# Mynd_Main.net
KiCad netlist of a schematic drawn in Altium Designer
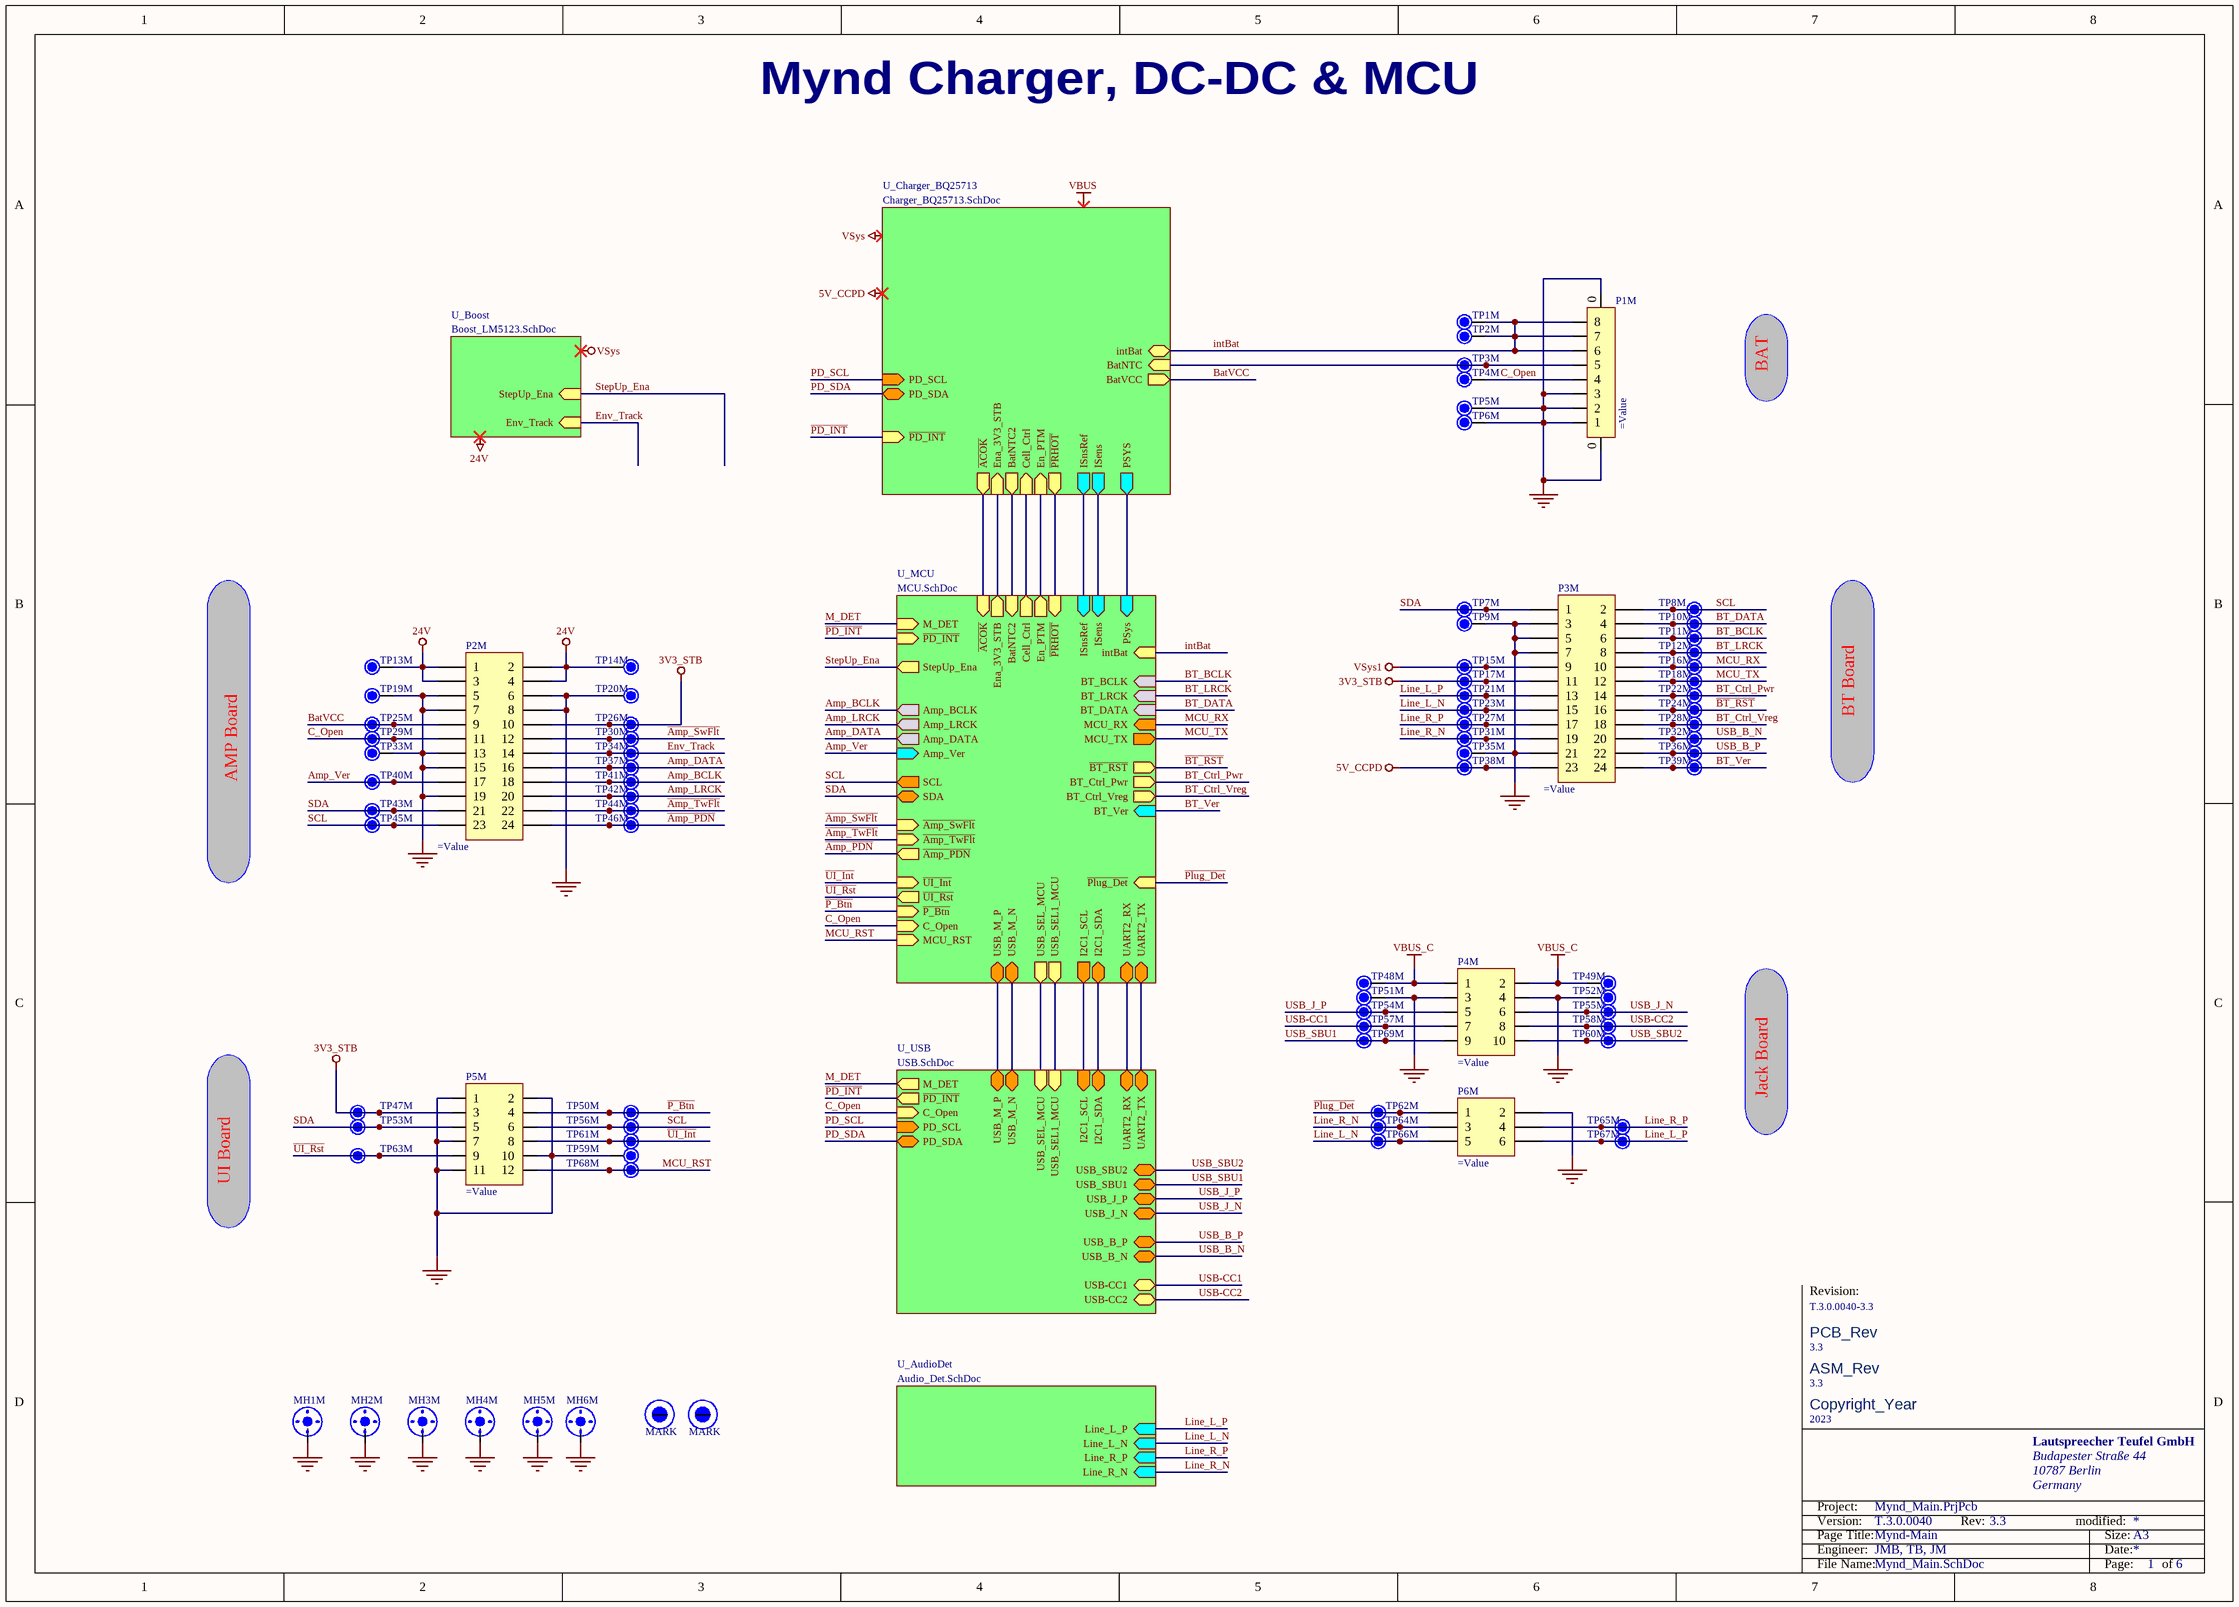
[diagram p0: Mynd_Main.SchDoc]

(export (version "E")
  (design (tool "Eeschema 10.0.6"))
  (components
    (comp (ref "MH1M")
      (value "SCREW_HOLE_D30")
      (footprint "SCREW_D30")
      (libsource (lib "altium-import") (part "root_1_SCREW_HOLE_"))
    )
    (comp (ref "MH2M")
      (value "SCREW_HOLE_D30")
      (footprint "SCREW_D30")
      (libsource (lib "altium-import") (part "root_1_SCREW_HOLE_"))
    )
    (comp (ref "MH3M")
      (value "SCREW_HOLE_D30")
      (footprint "SCREW_D30")
      (libsource (lib "altium-import") (part "root_1_SCREW_HOLE_"))
    )
    (comp (ref "MH4M")
      (value "SCREW_HOLE_D30")
      (footprint "SCREW_D30")
      (libsource (lib "altium-import") (part "root_1_SCREW_HOLE_"))
    )
    (comp (ref "MH5M")
      (value "SCREW_HOLE_D30")
      (footprint "SCREW_D30")
      (libsource (lib "altium-import") (part "root_1_SCREW_HOLE_"))
    )
    (comp (ref "MH6M")
      (value "SCREW_HOLE_D30")
      (footprint "SCREW_D30")
      (libsource (lib "altium-import") (part "root_1_SCREW_HOLE_"))
    )
    (comp (ref "MK1M")
      (value "MARK")
      (footprint "MARK")
      (description "MARK DOT")
      (libsource (lib "altium-import") (part "root_0_MARK_"))
    )
    (comp (ref "MK2M")
      (value "MARK")
      (footprint "MARK")
      (description "MARK DOT")
      (libsource (lib "altium-import") (part "root_0_MARK_"))
    )
    (comp (ref "P1M")
      (value "~")
      (footprint "CON_250_SMD_H_8P")
      (description "SMD WTB CONNECTOR 8P P2.5mm TIN")
      (fields (field (name "PART_NUMBER") "WT250MW-084R-0W"))
      (libsource (lib "altium-import") (part "root_2_CON 8P_F_"))
    )
    (comp (ref "P2M")
      (value "~")
      (footprint "Female_SMD_Bottom_2X12_254")
      (description "SMD BTB CONNECTOR 24P P2.54mm GOLD")
      (fields
        (field (name "MANUFACTURER") "MINGHENG")
        (field (name "PART_NUMBER") "2.54FH 2x12Pin H3.55 SMT")
      )
      (libsource (lib "altium-import") (part "root_0_CON 2x12P_"))
    )
    (comp (ref "P3M")
      (value "~")
      (footprint "Female_SMD_Bottom_2X12_254")
      (description "SMD BTB CONNECTOR 24P P2.54mm GOLD")
      (fields
        (field (name "MANUFACTURER") "MINGHENG")
        (field (name "PART_NUMBER") "2.54FH 2x12Pin H3.55 SMT")
      )
      (libsource (lib "altium-import") (part "root_0_CON 2x12P_"))
    )
    (comp (ref "P4M")
      (value "~")
      (footprint "WB200AL_2x5P")
      (description "SMD WTB CONNECTOR 10P P2.0mm TIN")
      (fields (field (name "MANUFACTURER") "MINGHENG") (field (name "PART_NUMBER") "WB200AL-10"))
      (libsource (lib "altium-import") (part "root_0_CON 2X5P_"))
    )
    (comp (ref "P5M")
      (value "~")
      (footprint "WB200AL_2x6P")
      (description "SMD WTB CONNECTOR 12P P2.0mm TIN")
      (fields (field (name "MANUFACTURER") "MINGHENG") (field (name "PART_NUMBER") "WB200AL-12"))
      (libsource (lib "altium-import") (part "root_0_CON 2X6P_"))
    )
    (comp (ref "P6M")
      (value "~")
      (footprint "WB200AL_2x3P")
      (description "SMD WTB CONNECTOR 6P P2.0mm TIN")
      (fields (field (name "MANUFACTURER") "MINGHENG") (field (name "PART_NUMBER") "WB200AL-06"))
      (libsource (lib "altium-import") (part "root_0_CON 2X3P_"))
    )
    (comp (ref "Teufel_ASM_Label1M")
      (value "3.3")
      (footprint "Teufel_ASM_Rev")
      (description "Teufel_ASM_Rev")
      (libsource (lib "altium-import") (part "root_0_Teufel_ASM_Label_"))
    )
    (comp (ref "Teufel_Copyright1M")
      (value "~")
      (footprint "TEUFEL_COPYRIGHT")
      (description "Teufel_Copyright_Year")
      (libsource (lib "altium-import") (part "root_0_Teufel_Copyright_"))
    )
    (comp (ref "Teufel_PCB_Label1M")
      (value "3.3")
      (footprint "Teufel_PCB_Rev")
      (description "Teufel_PCB_Label")
      (libsource (lib "altium-import") (part "root_0_Teufel_PCB_Label_"))
    )
    (comp (ref "Teufel_PCB_Logo1M")
      (value "-3.3")
      (footprint "Teufel_NoLogo")
      (description "Teufel PCB NoLogo")
      (libsource (lib "altium-import") (part "root_0_Teufel NoLogo_"))
    )
    (comp (ref "TP1M")
      (value "TP12")
      (footprint "TP120")
      (description "Test Point")
      (libsource (lib "altium-import") (part "root_0_mirrored_TP_"))
    )
    (comp (ref "TP2M")
      (value "TP12")
      (footprint "TP120")
      (description "Test Point")
      (libsource (lib "altium-import") (part "root_0_mirrored_TP_"))
    )
    (comp (ref "TP3M")
      (value "TP12")
      (footprint "TP120")
      (description "Test Point")
      (libsource (lib "altium-import") (part "root_0_mirrored_TP_"))
    )
    (comp (ref "TP4M")
      (value "TP12")
      (footprint "TP120")
      (description "Test Point")
      (libsource (lib "altium-import") (part "root_0_mirrored_TP_"))
    )
    (comp (ref "TP5M")
      (value "TP12")
      (footprint "TP120")
      (description "Test Point")
      (libsource (lib "altium-import") (part "root_0_mirrored_TP_"))
    )
    (comp (ref "TP6M")
      (value "TP12")
      (footprint "TP120")
      (description "Test Point")
      (libsource (lib "altium-import") (part "root_0_mirrored_TP_"))
    )
    (comp (ref "TP7M")
      (value "TP12")
      (footprint "TP120")
      (description "Test Point")
      (libsource (lib "altium-import") (part "root_0_mirrored_TP_"))
    )
    (comp (ref "TP8M")
      (value "TP12")
      (footprint "TP120")
      (description "Test Point")
      (libsource (lib "altium-import") (part "root_0_TP_"))
    )
    (comp (ref "TP9M")
      (value "TP12")
      (footprint "TP120")
      (description "Test Point")
      (libsource (lib "altium-import") (part "root_0_mirrored_TP_"))
    )
    (comp (ref "TP10M")
      (value "TP12")
      (footprint "TP120")
      (description "Test Point")
      (libsource (lib "altium-import") (part "root_0_TP_"))
    )
    (comp (ref "TP11M")
      (value "TP12")
      (footprint "TP120")
      (description "Test Point")
      (libsource (lib "altium-import") (part "root_0_TP_"))
    )
    (comp (ref "TP12M")
      (value "TP12")
      (footprint "TP120")
      (description "Test Point")
      (libsource (lib "altium-import") (part "root_0_TP_"))
    )
    (comp (ref "TP13M")
      (value "TP12")
      (footprint "TP120")
      (description "Test Point")
      (libsource (lib "altium-import") (part "root_0_mirrored_TP_"))
    )
    (comp (ref "TP14M")
      (value "TP12")
      (footprint "TP120")
      (description "Test Point")
      (libsource (lib "altium-import") (part "root_0_TP_"))
    )
    (comp (ref "TP15M")
      (value "TP12")
      (footprint "TP120")
      (description "Test Point")
      (libsource (lib "altium-import") (part "root_0_mirrored_TP_"))
    )
    (comp (ref "TP16M")
      (value "TP12")
      (footprint "TP120")
      (description "Test Point")
      (libsource (lib "altium-import") (part "root_0_TP_"))
    )
    (comp (ref "TP17M")
      (value "TP12")
      (footprint "TP120")
      (description "Test Point")
      (libsource (lib "altium-import") (part "root_0_mirrored_TP_"))
    )
    (comp (ref "TP18M")
      (value "TP12")
      (footprint "TP120")
      (description "Test Point")
      (libsource (lib "altium-import") (part "root_0_TP_"))
    )
    (comp (ref "TP19M")
      (value "TP12")
      (footprint "TP120")
      (description "Test Point")
      (libsource (lib "altium-import") (part "root_0_mirrored_TP_"))
    )
    (comp (ref "TP20M")
      (value "TP12")
      (footprint "TP120")
      (description "Test Point")
      (libsource (lib "altium-import") (part "root_0_TP_"))
    )
    (comp (ref "TP21M")
      (value "TP12")
      (footprint "TP120")
      (description "Test Point")
      (libsource (lib "altium-import") (part "root_0_mirrored_TP_"))
    )
    (comp (ref "TP22M")
      (value "TP12")
      (footprint "TP120")
      (description "Test Point")
      (libsource (lib "altium-import") (part "root_0_TP_"))
    )
    (comp (ref "TP23M")
      (value "TP12")
      (footprint "TP120")
      (description "Test Point")
      (libsource (lib "altium-import") (part "root_0_mirrored_TP_"))
    )
    (comp (ref "TP24M")
      (value "TP12")
      (footprint "TP120")
      (description "Test Point")
      (libsource (lib "altium-import") (part "root_0_TP_"))
    )
    (comp (ref "TP25M")
      (value "TP12")
      (footprint "TP120")
      (description "Test Point")
      (libsource (lib "altium-import") (part "root_0_mirrored_TP_"))
    )
    (comp (ref "TP26M")
      (value "TP12")
      (footprint "TP120")
      (description "Test Point")
      (libsource (lib "altium-import") (part "root_0_TP_"))
    )
    (comp (ref "TP27M")
      (value "TP12")
      (footprint "TP120")
      (description "Test Point")
      (libsource (lib "altium-import") (part "root_0_mirrored_TP_"))
    )
    (comp (ref "TP28M")
      (value "TP12")
      (footprint "TP120")
      (description "Test Point")
      (libsource (lib "altium-import") (part "root_0_TP_"))
    )
    (comp (ref "TP29M")
      (value "TP12")
      (footprint "TP120")
      (description "Test Point")
      (libsource (lib "altium-import") (part "root_0_mirrored_TP_"))
    )
    (comp (ref "TP30M")
      (value "TP12")
      (footprint "TP120")
      (description "Test Point")
      (libsource (lib "altium-import") (part "root_0_TP_"))
    )
    (comp (ref "TP31M")
      (value "TP12")
      (footprint "TP120")
      (description "Test Point")
      (libsource (lib "altium-import") (part "root_0_mirrored_TP_"))
    )
    (comp (ref "TP32M")
      (value "TP12")
      (footprint "TP120")
      (description "Test Point")
      (libsource (lib "altium-import") (part "root_0_TP_"))
    )
    (comp (ref "TP33M")
      (value "TP12")
      (footprint "TP120")
      (description "Test Point")
      (libsource (lib "altium-import") (part "root_0_mirrored_TP_"))
    )
    (comp (ref "TP34M")
      (value "TP12")
      (footprint "TP120")
      (description "Test Point")
      (libsource (lib "altium-import") (part "root_0_TP_"))
    )
    (comp (ref "TP35M")
      (value "TP12")
      (footprint "TP120")
      (description "Test Point")
      (libsource (lib "altium-import") (part "root_0_mirrored_TP_"))
    )
    (comp (ref "TP36M")
      (value "TP12")
      (footprint "TP120")
      (description "Test Point")
      (libsource (lib "altium-import") (part "root_0_TP_"))
    )
    (comp (ref "TP37M")
      (value "TP12")
      (footprint "TP120")
      (description "Test Point")
      (libsource (lib "altium-import") (part "root_0_TP_"))
    )
    (comp (ref "TP38M")
      (value "TP12")
      (footprint "TP120")
      (description "Test Point")
      (libsource (lib "altium-import") (part "root_0_mirrored_TP_"))
    )
    (comp (ref "TP39M")
      (value "TP12")
      (footprint "TP120")
      (description "Test Point")
      (libsource (lib "altium-import") (part "root_0_TP_"))
    )
    (comp (ref "TP40M")
      (value "TP12")
      (footprint "TP120")
      (description "Test Point")
      (libsource (lib "altium-import") (part "root_0_mirrored_TP_"))
    )
    (comp (ref "TP41M")
      (value "TP12")
      (footprint "TP120")
      (description "Test Point")
      (libsource (lib "altium-import") (part "root_0_TP_"))
    )
    (comp (ref "TP42M")
      (value "TP12")
      (footprint "TP120")
      (description "Test Point")
      (libsource (lib "altium-import") (part "root_0_TP_"))
    )
    (comp (ref "TP43M")
      (value "TP12")
      (footprint "TP120")
      (description "Test Point")
      (libsource (lib "altium-import") (part "root_0_mirrored_TP_"))
    )
    (comp (ref "TP44M")
      (value "TP12")
      (footprint "TP120")
      (description "Test Point")
      (libsource (lib "altium-import") (part "root_0_TP_"))
    )
    (comp (ref "TP45M")
      (value "TP12")
      (footprint "TP120")
      (description "Test Point")
      (libsource (lib "altium-import") (part "root_0_mirrored_TP_"))
    )
    (comp (ref "TP46M")
      (value "TP12")
      (footprint "TP120")
      (description "Test Point")
      (libsource (lib "altium-import") (part "root_0_TP_"))
    )
    (comp (ref "TP47M")
      (value "TP12")
      (footprint "TP120")
      (description "Test Point")
      (libsource (lib "altium-import") (part "root_0_mirrored_TP_"))
    )
    (comp (ref "TP48M")
      (value "TP12")
      (footprint "TP120")
      (description "Test Point")
      (libsource (lib "altium-import") (part "root_0_mirrored_TP_"))
    )
    (comp (ref "TP49M")
      (value "TP12")
      (footprint "TP120")
      (description "Test Point")
      (libsource (lib "altium-import") (part "root_0_TP_"))
    )
    (comp (ref "TP50M")
      (value "TP12")
      (footprint "TP120")
      (description "Test Point")
      (libsource (lib "altium-import") (part "root_0_TP_"))
    )
    (comp (ref "TP51M")
      (value "TP12")
      (footprint "TP120")
      (description "Test Point")
      (libsource (lib "altium-import") (part "root_0_mirrored_TP_"))
    )
    (comp (ref "TP52M")
      (value "TP12")
      (footprint "TP120")
      (description "Test Point")
      (libsource (lib "altium-import") (part "root_0_TP_"))
    )
    (comp (ref "TP53M")
      (value "TP12")
      (footprint "TP120")
      (description "Test Point")
      (libsource (lib "altium-import") (part "root_0_mirrored_TP_"))
    )
    (comp (ref "TP54M")
      (value "TP12")
      (footprint "TP120")
      (description "Test Point")
      (libsource (lib "altium-import") (part "root_0_mirrored_TP_"))
    )
    (comp (ref "TP55M")
      (value "TP12")
      (footprint "TP120")
      (description "Test Point")
      (libsource (lib "altium-import") (part "root_0_TP_"))
    )
    (comp (ref "TP56M")
      (value "TP12")
      (footprint "TP120")
      (description "Test Point")
      (libsource (lib "altium-import") (part "root_0_TP_"))
    )
    (comp (ref "TP57M")
      (value "TP12")
      (footprint "TP120")
      (description "Test Point")
      (libsource (lib "altium-import") (part "root_0_mirrored_TP_"))
    )
    (comp (ref "TP58M")
      (value "TP12")
      (footprint "TP120")
      (description "Test Point")
      (libsource (lib "altium-import") (part "root_0_TP_"))
    )
    (comp (ref "TP59M")
      (value "TP12")
      (footprint "TP120")
      (description "Test Point")
      (libsource (lib "altium-import") (part "root_0_TP_"))
    )
    (comp (ref "TP60M")
      (value "TP12")
      (footprint "TP120")
      (description "Test Point")
      (libsource (lib "altium-import") (part "root_0_TP_"))
    )
    (comp (ref "TP61M")
      (value "TP12")
      (footprint "TP120")
      (description "Test Point")
      (libsource (lib "altium-import") (part "root_0_TP_"))
    )
    (comp (ref "TP62M")
      (value "TP12")
      (footprint "TP120")
      (description "Test Point")
      (libsource (lib "altium-import") (part "root_0_mirrored_TP_"))
    )
    (comp (ref "TP63M")
      (value "TP12")
      (footprint "TP120")
      (description "Test Point")
      (libsource (lib "altium-import") (part "root_0_mirrored_TP_"))
    )
    (comp (ref "TP64M")
      (value "TP12")
      (footprint "TP120")
      (description "Test Point")
      (libsource (lib "altium-import") (part "root_0_mirrored_TP_"))
    )
    (comp (ref "TP65M")
      (value "TP12")
      (footprint "TP120")
      (description "Test Point")
      (libsource (lib "altium-import") (part "root_0_TP_"))
    )
    (comp (ref "TP66M")
      (value "TP12")
      (footprint "TP120")
      (description "Test Point")
      (libsource (lib "altium-import") (part "root_0_mirrored_TP_"))
    )
    (comp (ref "TP67M")
      (value "TP12")
      (footprint "TP120")
      (description "Test Point")
      (libsource (lib "altium-import") (part "root_0_TP_"))
    )
    (comp (ref "TP68M")
      (value "TP12")
      (footprint "TP120")
      (description "Test Point")
      (libsource (lib "altium-import") (part "root_0_TP_"))
    )
    (comp (ref "TP69M")
      (value "TP12")
      (footprint "TP120")
      (description "Test Point")
      (libsource (lib "altium-import") (part "root_0_mirrored_TP_"))
    )
  )
  (nets
    (net (code "2") (name "/Amp_BCLK") (class "Default")
      (node (ref "P2M") (pin "18") (pinfunction "18_18") (pintype "passive"))
      (node (ref "TP41M") (pin "1") (pinfunction "1_1") (pintype "passive"))
    )
    (net (code "3") (name "/Amp_DATA") (class "Default")
      (node (ref "P2M") (pin "16") (pinfunction "16_16") (pintype "passive"))
      (node (ref "TP37M") (pin "1") (pinfunction "1_1") (pintype "passive"))
    )
    (net (code "4") (name "/Amp_LRCK") (class "Default")
      (node (ref "P2M") (pin "20") (pinfunction "20_20") (pintype "passive"))
      (node (ref "TP42M") (pin "1") (pinfunction "1_1") (pintype "passive"))
    )
    (net (code "5") (name "/Amp_Ver") (class "Default")
      (node (ref "P2M") (pin "17") (pinfunction "17_17") (pintype "passive"))
      (node (ref "TP40M") (pin "1") (pinfunction "1_1") (pintype "passive"))
    )
    (net (code "6") (name "/BT_BCLK") (class "Default")
      (node (ref "P3M") (pin "6") (pinfunction "6_6") (pintype "passive"))
      (node (ref "TP11M") (pin "1") (pinfunction "1_1") (pintype "passive"))
    )
    (net (code "7") (name "/BT_Ctrl_Pwr") (class "Default")
      (node (ref "P3M") (pin "14") (pinfunction "14_14") (pintype "passive"))
      (node (ref "TP22M") (pin "1") (pinfunction "1_1") (pintype "passive"))
    )
    (net (code "8") (name "/BT_Ctrl_Vreg") (class "Default")
      (node (ref "P3M") (pin "18") (pinfunction "18_18") (pintype "passive"))
      (node (ref "TP28M") (pin "1") (pinfunction "1_1") (pintype "passive"))
    )
    (net (code "9") (name "/BT_DATA") (class "Default")
      (node (ref "P3M") (pin "4") (pinfunction "4_4") (pintype "passive"))
      (node (ref "TP10M") (pin "1") (pinfunction "1_1") (pintype "passive"))
    )
    (net (code "10") (name "/BT_LRCK") (class "Default")
      (node (ref "P3M") (pin "8") (pinfunction "8_8") (pintype "passive"))
      (node (ref "TP12M") (pin "1") (pinfunction "1_1") (pintype "passive"))
    )
    (net (code "11") (name "/BT_RST") (class "Default")
      (node (ref "P3M") (pin "16") (pinfunction "16_16") (pintype "passive"))
      (node (ref "TP24M") (pin "1") (pinfunction "1_1") (pintype "passive"))
    )
    (net (code "12") (name "/BT_Ver") (class "Default")
      (node (ref "P3M") (pin "24") (pinfunction "24_24") (pintype "passive"))
      (node (ref "TP39M") (pin "1") (pinfunction "1_1") (pintype "passive"))
    )
    (net (code "13") (name "/BatNTC") (class "Default")
      (node (ref "P1M") (pin "5") (pinfunction "5_5") (pintype "passive"))
      (node (ref "TP3M") (pin "1") (pinfunction "1_1") (pintype "passive"))
    )
    (net (code "15") (name "/BatVCC") (class "Default")
      (node (ref "P2M") (pin "9") (pinfunction "9_9") (pintype "passive"))
      (node (ref "TP25M") (pin "1") (pinfunction "1_1") (pintype "passive"))
    )
    (net (code "16") (name "/C_Open") (class "Default")
      (node (ref "P1M") (pin "4") (pinfunction "4_4") (pintype "passive"))
      (node (ref "P2M") (pin "11") (pinfunction "11_11") (pintype "passive"))
      (node (ref "TP29M") (pin "1") (pinfunction "1_1") (pintype "passive"))
      (node (ref "TP4M") (pin "1") (pinfunction "1_1") (pintype "passive"))
    )
    (net (code "20") (name "/Env_Track") (class "Default")
      (node (ref "P2M") (pin "14") (pinfunction "14_14") (pintype "passive"))
      (node (ref "TP34M") (pin "1") (pinfunction "1_1") (pintype "passive"))
    )
    (net (code "25") (name "/Line_L_N") (class "Default")
      (node (ref "P3M") (pin "15") (pinfunction "15_15") (pintype "passive"))
      (node (ref "P6M") (pin "5") (pinfunction "5_5") (pintype "passive"))
      (node (ref "TP23M") (pin "1") (pinfunction "1_1") (pintype "passive"))
      (node (ref "TP66M") (pin "1") (pinfunction "1_1") (pintype "passive"))
    )
    (net (code "26") (name "/Line_L_P") (class "Default")
      (node (ref "P3M") (pin "13") (pinfunction "13_13") (pintype "passive"))
      (node (ref "P6M") (pin "6") (pinfunction "6_6") (pintype "passive"))
      (node (ref "TP21M") (pin "1") (pinfunction "1_1") (pintype "passive"))
      (node (ref "TP67M") (pin "1") (pinfunction "1_1") (pintype "passive"))
    )
    (net (code "27") (name "/Line_R_N") (class "Default")
      (node (ref "P3M") (pin "19") (pinfunction "19_19") (pintype "passive"))
      (node (ref "P6M") (pin "3") (pinfunction "3_3") (pintype "passive"))
      (node (ref "TP31M") (pin "1") (pinfunction "1_1") (pintype "passive"))
      (node (ref "TP64M") (pin "1") (pinfunction "1_1") (pintype "passive"))
    )
    (net (code "28") (name "/Line_R_P") (class "Default")
      (node (ref "P3M") (pin "17") (pinfunction "17_17") (pintype "passive"))
      (node (ref "P6M") (pin "4") (pinfunction "4_4") (pintype "passive"))
      (node (ref "TP27M") (pin "1") (pinfunction "1_1") (pintype "passive"))
      (node (ref "TP65M") (pin "1") (pinfunction "1_1") (pintype "passive"))
    )
    (net (code "29") (name "/MCU_RST") (class "Default")
      (node (ref "P5M") (pin "12") (pinfunction "12_12") (pintype "passive"))
      (node (ref "TP68M") (pin "1") (pinfunction "1_1") (pintype "passive"))
    )
    (net (code "30") (name "/MCU_RX") (class "Default")
      (node (ref "P3M") (pin "10") (pinfunction "10_10") (pintype "passive"))
      (node (ref "TP16M") (pin "1") (pinfunction "1_1") (pintype "passive"))
    )
    (net (code "31") (name "/MCU_TX") (class "Default")
      (node (ref "P3M") (pin "12") (pinfunction "12_12") (pintype "passive"))
      (node (ref "TP18M") (pin "1") (pinfunction "1_1") (pintype "passive"))
    )
    (net (code "38") (name "/P_Btn") (class "Default")
      (node (ref "P5M") (pin "4") (pinfunction "4_4") (pintype "passive"))
      (node (ref "TP50M") (pin "1") (pinfunction "1_1") (pintype "passive"))
    )
    (net (code "39") (name "/Plug_Det") (class "Default")
      (node (ref "P6M") (pin "1") (pinfunction "1_1") (pintype "passive"))
      (node (ref "TP62M") (pin "1") (pinfunction "1_1") (pintype "passive"))
    )
    (net (code "40") (name "/SCL") (class "Default")
      (node (ref "P2M") (pin "23") (pinfunction "23_23") (pintype "passive"))
      (node (ref "P3M") (pin "2") (pinfunction "2_2") (pintype "passive"))
      (node (ref "P5M") (pin "6") (pinfunction "6_6") (pintype "passive"))
      (node (ref "TP45M") (pin "1") (pinfunction "1_1") (pintype "passive"))
      (node (ref "TP56M") (pin "1") (pinfunction "1_1") (pintype "passive"))
      (node (ref "TP8M") (pin "1") (pinfunction "1_1") (pintype "passive"))
    )
    (net (code "41") (name "/SDA") (class "Default")
      (node (ref "P2M") (pin "21") (pinfunction "21_21") (pintype "passive"))
      (node (ref "P3M") (pin "1") (pinfunction "1_1") (pintype "passive"))
      (node (ref "P5M") (pin "5") (pinfunction "5_5") (pintype "passive"))
      (node (ref "TP43M") (pin "1") (pinfunction "1_1") (pintype "passive"))
      (node (ref "TP53M") (pin "1") (pinfunction "1_1") (pintype "passive"))
      (node (ref "TP7M") (pin "1") (pinfunction "1_1") (pintype "passive"))
    )
    (net (code "45") (name "/UI_Int") (class "Default")
      (node (ref "P5M") (pin "8") (pinfunction "8_8") (pintype "passive"))
      (node (ref "TP61M") (pin "1") (pinfunction "1_1") (pintype "passive"))
    )
    (net (code "46") (name "/UI_Rst") (class "Default")
      (node (ref "P5M") (pin "9") (pinfunction "9_9") (pintype "passive"))
      (node (ref "TP63M") (pin "1") (pinfunction "1_1") (pintype "passive"))
    )
    (net (code "47") (name "/USB-CC1") (class "Default")
      (node (ref "P4M") (pin "7") (pinfunction "7_7") (pintype "passive"))
      (node (ref "TP57M") (pin "1") (pinfunction "1_1") (pintype "passive"))
    )
    (net (code "48") (name "/USB-CC2") (class "Default")
      (node (ref "P4M") (pin "8") (pinfunction "8_8") (pintype "passive"))
      (node (ref "TP58M") (pin "1") (pinfunction "1_1") (pintype "passive"))
    )
    (net (code "49") (name "/USB_B_N") (class "Default")
      (node (ref "P3M") (pin "20") (pinfunction "20_20") (pintype "passive"))
      (node (ref "TP32M") (pin "1") (pinfunction "1_1") (pintype "passive"))
    )
    (net (code "50") (name "/USB_B_P") (class "Default")
      (node (ref "P3M") (pin "22") (pinfunction "22_22") (pintype "passive"))
      (node (ref "TP36M") (pin "1") (pinfunction "1_1") (pintype "passive"))
    )
    (net (code "51") (name "/USB_J_N") (class "Default")
      (node (ref "P4M") (pin "6") (pinfunction "6_6") (pintype "passive"))
      (node (ref "TP55M") (pin "1") (pinfunction "1_1") (pintype "passive"))
    )
    (net (code "52") (name "/USB_J_P") (class "Default")
      (node (ref "P4M") (pin "5") (pinfunction "5_5") (pintype "passive"))
      (node (ref "TP54M") (pin "1") (pinfunction "1_1") (pintype "passive"))
    )
    (net (code "55") (name "/USB_SBU1") (class "Default")
      (node (ref "P4M") (pin "9") (pinfunction "9_9") (pintype "passive"))
      (node (ref "TP69M") (pin "1") (pinfunction "1_1") (pintype "passive"))
    )
    (net (code "56") (name "/USB_SBU2") (class "Default")
      (node (ref "P4M") (pin "10") (pinfunction "10_10") (pintype "passive"))
      (node (ref "TP60M") (pin "1") (pinfunction "1_1") (pintype "passive"))
    )
    (net (code "59") (name "/intBat") (class "Default")
      (node (ref "P1M") (pin "6") (pinfunction "6_6") (pintype "passive"))
      (node (ref "P1M") (pin "7") (pinfunction "7_7") (pintype "passive"))
      (node (ref "P1M") (pin "8") (pinfunction "8_8") (pintype "passive"))
      (node (ref "TP1M") (pin "1") (pinfunction "1_1") (pintype "passive"))
      (node (ref "TP2M") (pin "1") (pinfunction "1_1") (pintype "passive"))
    )
    (net (code "60") (name "/~{Amp_PDN}") (class "Default")
      (node (ref "P2M") (pin "24") (pinfunction "24_24") (pintype "passive"))
      (node (ref "TP46M") (pin "1") (pinfunction "1_1") (pintype "passive"))
    )
    (net (code "61") (name "/~{Amp_SwFlt}") (class "Default")
      (node (ref "P2M") (pin "12") (pinfunction "12_12") (pintype "passive"))
      (node (ref "TP30M") (pin "1") (pinfunction "1_1") (pintype "passive"))
    )
    (net (code "62") (name "/~{Amp_TwFlt}") (class "Default")
      (node (ref "P2M") (pin "22") (pinfunction "22_22") (pintype "passive"))
      (node (ref "TP44M") (pin "1") (pinfunction "1_1") (pintype "passive"))
    )
    (net (code "63") (name "3V3_STB") (class "Default")
      (node (ref "P2M") (pin "10") (pinfunction "10_10") (pintype "passive"))
      (node (ref "P3M") (pin "11") (pinfunction "11_11") (pintype "passive"))
      (node (ref "P5M") (pin "3") (pinfunction "3_3") (pintype "passive"))
      (node (ref "TP17M") (pin "1") (pinfunction "1_1") (pintype "passive"))
      (node (ref "TP26M") (pin "1") (pinfunction "1_1") (pintype "passive"))
      (node (ref "TP47M") (pin "1") (pinfunction "1_1") (pintype "passive"))
    )
    (net (code "64") (name "5V_CCPD") (class "Default")
      (node (ref "P3M") (pin "23") (pinfunction "23_23") (pintype "passive"))
      (node (ref "TP38M") (pin "1") (pinfunction "1_1") (pintype "passive"))
    )
    (net (code "65") (name "24V") (class "Default")
      (node (ref "P2M") (pin "1") (pinfunction "1_1") (pintype "passive"))
      (node (ref "P2M") (pin "2") (pinfunction "2_2") (pintype "passive"))
      (node (ref "P2M") (pin "3") (pinfunction "3_3") (pintype "passive"))
      (node (ref "P2M") (pin "4") (pinfunction "4_4") (pintype "passive"))
      (node (ref "TP13M") (pin "1") (pinfunction "1_1") (pintype "passive"))
      (node (ref "TP14M") (pin "1") (pinfunction "1_1") (pintype "passive"))
    )
    (net (code "66") (name "GND") (class "Default")
      (node (ref "MH1M") (pin "1") (pinfunction "1_1") (pintype "passive"))
      (node (ref "MH2M") (pin "1") (pinfunction "1_1") (pintype "passive"))
      (node (ref "MH3M") (pin "1") (pinfunction "1_1") (pintype "passive"))
      (node (ref "MH4M") (pin "1") (pinfunction "1_1") (pintype "passive"))
      (node (ref "MH5M") (pin "1") (pinfunction "1_1") (pintype "passive"))
      (node (ref "MH6M") (pin "1") (pinfunction "1_1") (pintype "passive"))
      (node (ref "P1M") (pin "0") (pinfunction "0_0") (pintype "passive"))
      (node (ref "P1M") (pin "1") (pinfunction "1_1") (pintype "passive"))
      (node (ref "P1M") (pin "2") (pinfunction "2_2") (pintype "passive"))
      (node (ref "P1M") (pin "3") (pinfunction "3_3") (pintype "passive"))
      (node (ref "P2M") (pin "13") (pinfunction "13_13") (pintype "passive"))
      (node (ref "P2M") (pin "15") (pinfunction "15_15") (pintype "passive"))
      (node (ref "P2M") (pin "19") (pinfunction "19_19") (pintype "passive"))
      (node (ref "P2M") (pin "5") (pinfunction "5_5") (pintype "passive"))
      (node (ref "P2M") (pin "6") (pinfunction "6_6") (pintype "passive"))
      (node (ref "P2M") (pin "7") (pinfunction "7_7") (pintype "passive"))
      (node (ref "P2M") (pin "8") (pinfunction "8_8") (pintype "passive"))
      (node (ref "P3M") (pin "21") (pinfunction "21_21") (pintype "passive"))
      (node (ref "P3M") (pin "3") (pinfunction "3_3") (pintype "passive"))
      (node (ref "P3M") (pin "5") (pinfunction "5_5") (pintype "passive"))
      (node (ref "P3M") (pin "7") (pinfunction "7_7") (pintype "passive"))
      (node (ref "P4M") (pin "3") (pinfunction "3_3") (pintype "passive"))
      (node (ref "P4M") (pin "4") (pinfunction "4_4") (pintype "passive"))
      (node (ref "P5M") (pin "1") (pinfunction "1_1") (pintype "passive"))
      (node (ref "P5M") (pin "10") (pinfunction "10_10") (pintype "passive"))
      (node (ref "P5M") (pin "11") (pinfunction "11_11") (pintype "passive"))
      (node (ref "P5M") (pin "2") (pinfunction "2_2") (pintype "passive"))
      (node (ref "P5M") (pin "7") (pinfunction "7_7") (pintype "passive"))
      (node (ref "P6M") (pin "2") (pinfunction "2_2") (pintype "passive"))
      (node (ref "TP19M") (pin "1") (pinfunction "1_1") (pintype "passive"))
      (node (ref "TP20M") (pin "1") (pinfunction "1_1") (pintype "passive"))
      (node (ref "TP33M") (pin "1") (pinfunction "1_1") (pintype "passive"))
      (node (ref "TP35M") (pin "1") (pinfunction "1_1") (pintype "passive"))
      (node (ref "TP51M") (pin "1") (pinfunction "1_1") (pintype "passive"))
      (node (ref "TP52M") (pin "1") (pinfunction "1_1") (pintype "passive"))
      (node (ref "TP59M") (pin "1") (pinfunction "1_1") (pintype "passive"))
      (node (ref "TP5M") (pin "1") (pinfunction "1_1") (pintype "passive"))
      (node (ref "TP6M") (pin "1") (pinfunction "1_1") (pintype "passive"))
      (node (ref "TP9M") (pin "1") (pinfunction "1_1") (pintype "passive"))
    )
    (net (code "68") (name "VBUS_C") (class "Default")
      (node (ref "P4M") (pin "1") (pinfunction "1_1") (pintype "passive"))
      (node (ref "P4M") (pin "2") (pinfunction "2_2") (pintype "passive"))
      (node (ref "TP48M") (pin "1") (pinfunction "1_1") (pintype "passive"))
      (node (ref "TP49M") (pin "1") (pinfunction "1_1") (pintype "passive"))
    )
    (net (code "70") (name "VSys1") (class "Default")
      (node (ref "P3M") (pin "9") (pinfunction "9_9") (pintype "passive"))
      (node (ref "TP15M") (pin "1") (pinfunction "1_1") (pintype "passive"))
    )
    (net (code "71") (name "unconnected-(MK1M-PadMK_B)") (class "Default")
      (node (ref "MK1M") (pin "MK_B") (pinfunction "MK_B_MK_B") (pintype "passive"))
    )
    (net (code "72") (name "unconnected-(MK1M-PadMK_T)") (class "Default")
      (node (ref "MK1M") (pin "MK_T") (pinfunction "MK_T_MK_T") (pintype "passive"))
    )
    (net (code "73") (name "unconnected-(MK2M-PadMK_B)") (class "Default")
      (node (ref "MK2M") (pin "MK_B") (pinfunction "MK_B_MK_B") (pintype "passive"))
    )
    (net (code "74") (name "unconnected-(MK2M-PadMK_T)") (class "Default")
      (node (ref "MK2M") (pin "MK_T") (pinfunction "MK_T_MK_T") (pintype "passive"))
    )
  )
)
